# ETH10M100M_RMII_DP83825.net
KiCad netlist of a schematic drawn in Altium Designer
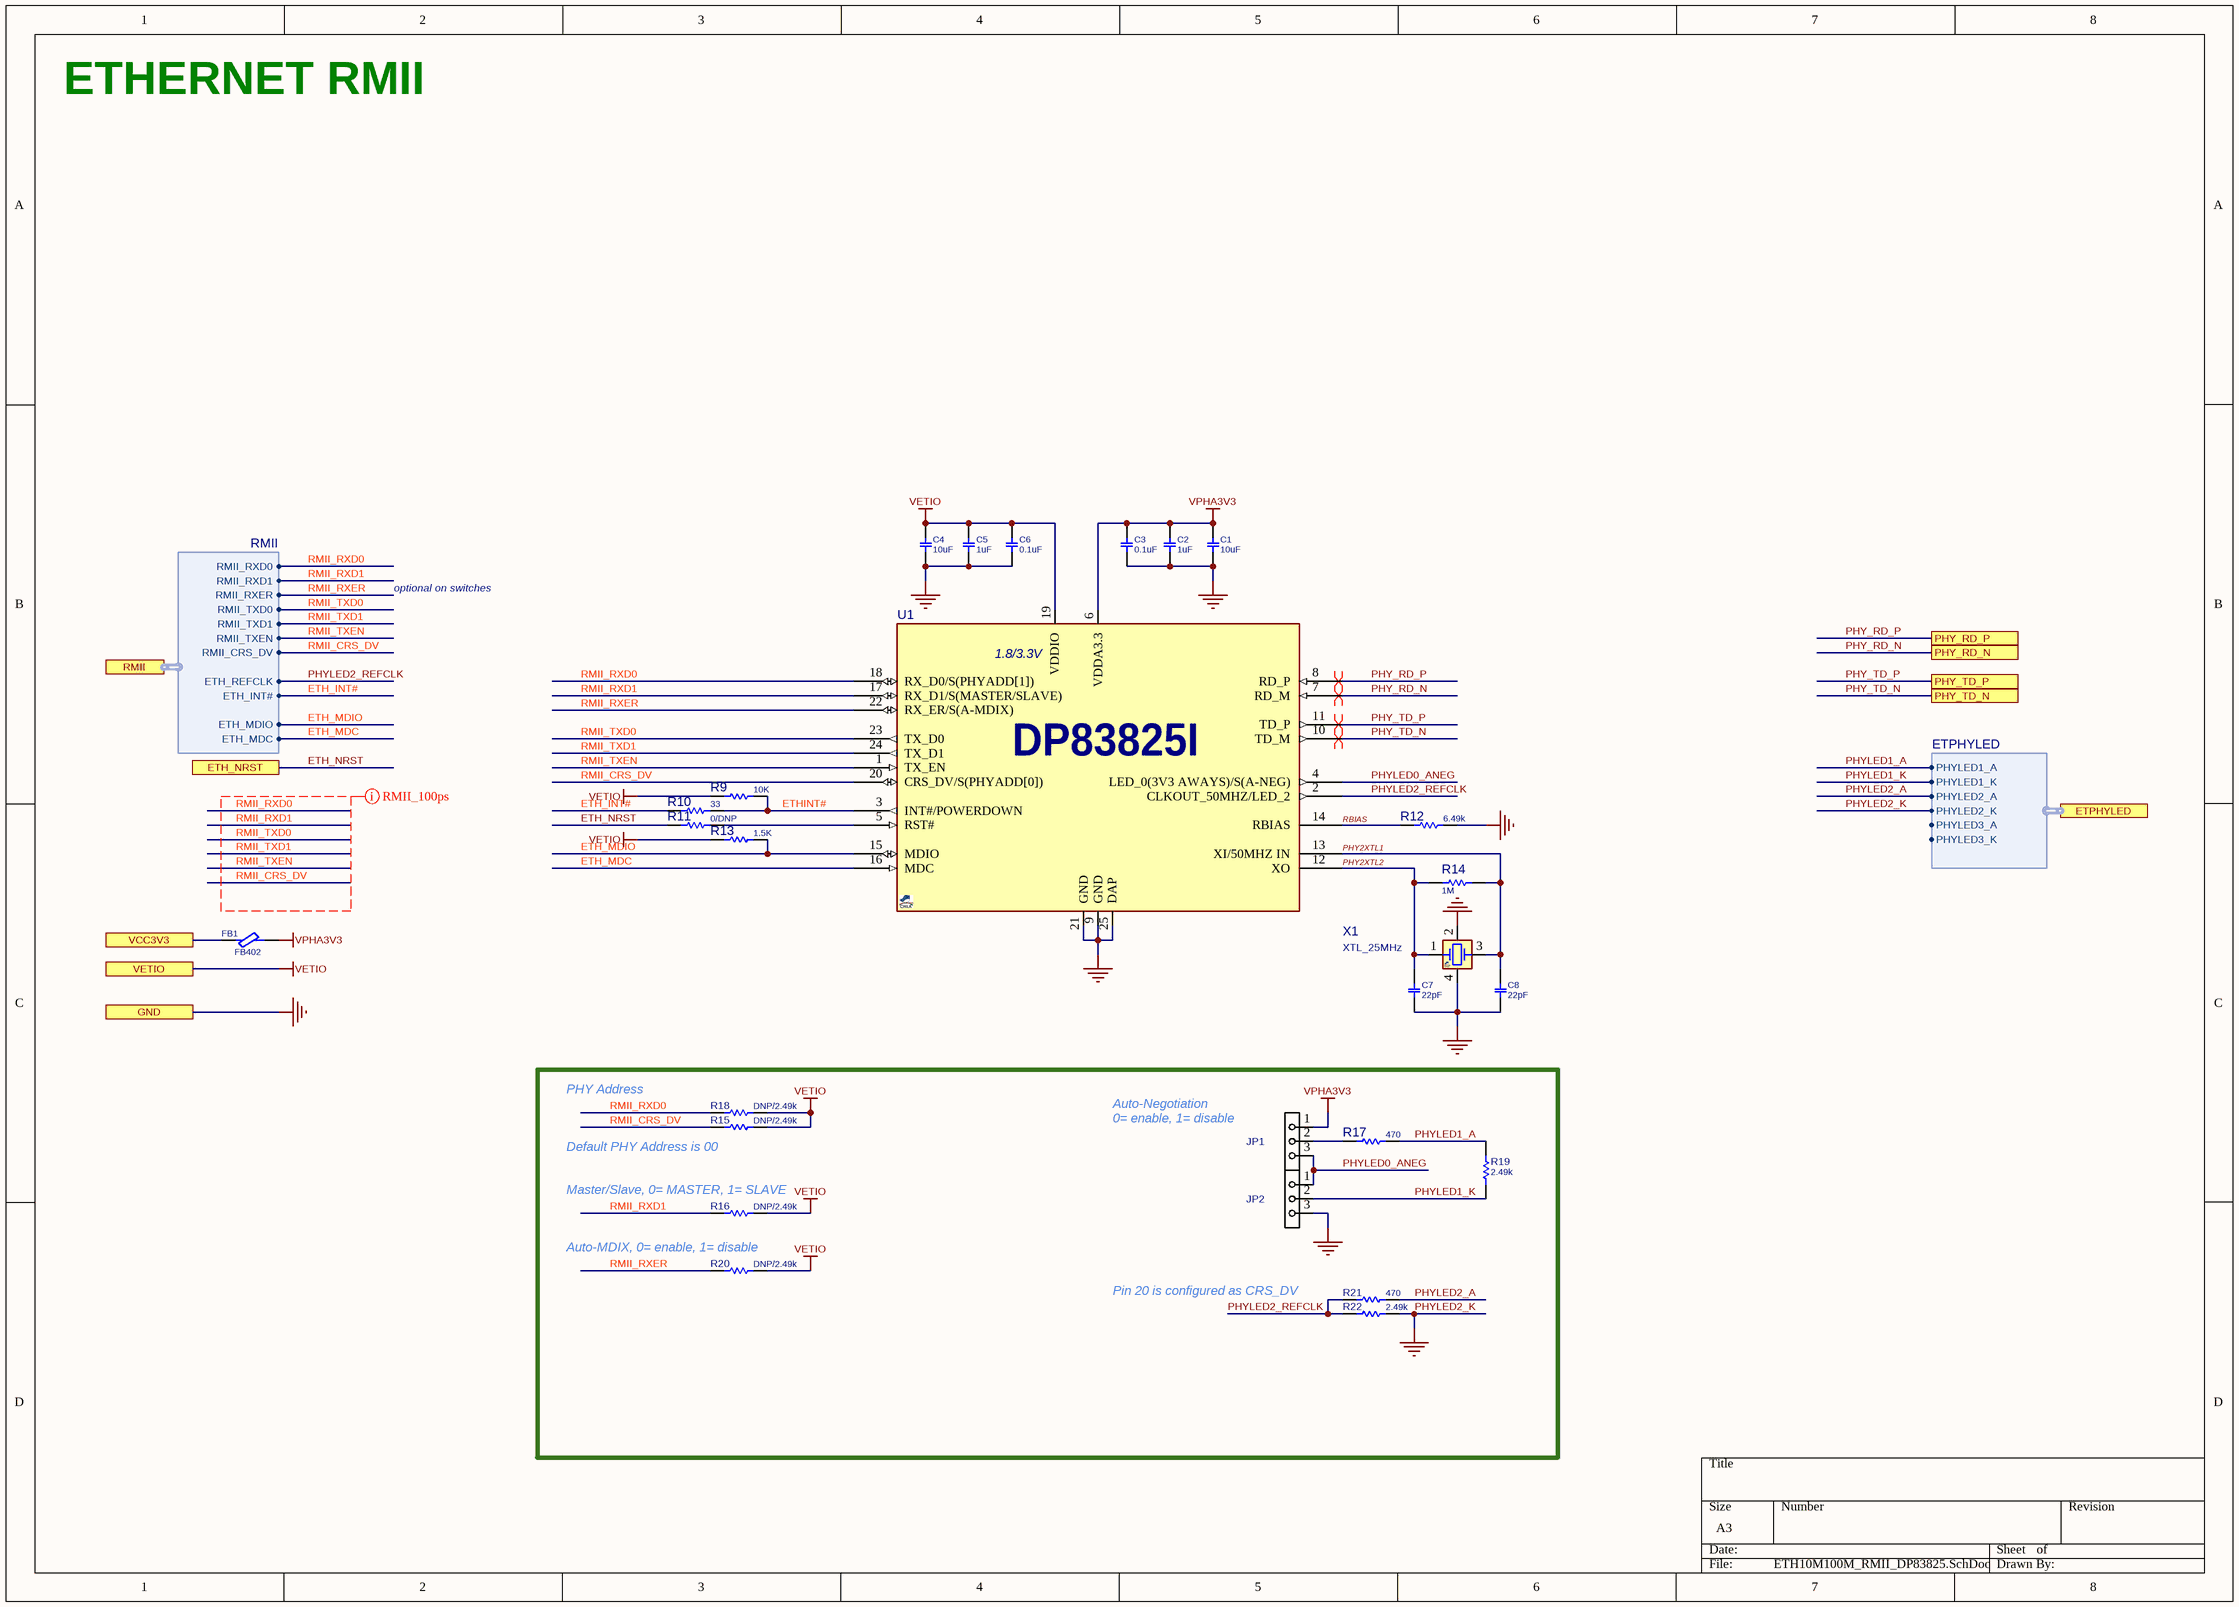
[diagram p0: ETH10M100M_RMII_DP83825.SchDoc]

(export (version "E")
  (design (tool "Eeschema 10.0.6"))
  (components
    (comp (ref "C1")
      (value "10uF")
      (footprint "C0402")
      (description "CAP, MLCC")
      (libsource (lib "mlcc_smd_passive") (part "CAP_SMD_MLCC_100n50TDK"))
    )
    (comp (ref "C2")
      (value "1uF")
      (footprint "C0402")
      (description "CAP, MLCC")
      (libsource (lib "mlcc_smd_passive") (part "CAP_SMD_MLCC_100n50TDK"))
    )
    (comp (ref "C3")
      (value "0.1uF")
      (footprint "C0402")
      (description "CAP, MLCC")
      (libsource (lib "mlcc_smd_passive") (part "CAP_SMD_MLCC_100n50TDK"))
    )
    (comp (ref "C4")
      (value "10uF")
      (footprint "C0402")
      (description "CAP, MLCC")
      (libsource (lib "mlcc_smd_passive") (part "CAP_SMD_MLCC_100n50TDK"))
    )
    (comp (ref "C5")
      (value "1uF")
      (footprint "C0402")
      (description "CAP, MLCC")
      (libsource (lib "mlcc_smd_passive") (part "CAP_SMD_MLCC_100n50TDK"))
    )
    (comp (ref "C6")
      (value "0.1uF")
      (footprint "C0402")
      (description "CAP, MLCC")
      (libsource (lib "mlcc_smd_passive") (part "CAP_SMD_MLCC_100n50TDK"))
    )
    (comp (ref "C7")
      (value "22pF")
      (footprint "C0402")
      (description "CAP, MLCC")
      (libsource (lib "mlcc_smd_passive") (part "CAP_SMD_MLCC_100n50TDK"))
    )
    (comp (ref "C8")
      (value "22pF")
      (footprint "C0402")
      (description "CAP, MLCC")
      (libsource (lib "mlcc_smd_passive") (part "CAP_SMD_MLCC_100n50TDK"))
    )
    (comp (ref "FB1")
      (value "FB402")
      (footprint "L0402")
      (description "FERRITE_Bead")
      (libsource (lib "emi_filter") (part "FBEAD_SMD_BLM18KG601"))
    )
    (comp (ref "JP1")
      (value "JMPHDR3PIN")
      (footprint "JP_3_60W")
      (description "JUMPER, HEADER 3PIN")
      (fields (field (name "MANF") "MANF") (field (name "MANF_P#") "MANF_P#"))
      (libsource (lib "test-tp_jumper") (part "JUMPER_SOLDER_3P"))
    )
    (comp (ref "JP2")
      (value "JMPHDR3PIN")
      (footprint "JP_3_60W")
      (description "JUMPER, HEADER 3PIN")
      (fields (field (name "MANF") "MANF") (field (name "MANF_P#") "MANF_P#"))
      (libsource (lib "test-tp_jumper") (part "JUMPER_SOLDER_3P"))
    )
    (comp (ref "R9")
      (value "10K")
      (footprint "R0402")
      (description "RESISTOR, SMD, THICK FILM, YAGEO")
      (fields (field (name "MANF_P#") "RC0402FR-071KL") (field (name "MANF") "Yageo"))
      (libsource (lib "res_smd_Yageo0402_thickfilm") (part "RES_SMD_1K_0402YK"))
    )
    (comp (ref "R10")
      (value "33")
      (footprint "R0402")
      (description "RESISTOR, SMD, THICK FILM, YAGEO")
      (fields (field (name "MANF_P#") "RC0402FR-071KL") (field (name "MANF") "Yageo"))
      (libsource (lib "res_smd_Yageo0402_thickfilm") (part "RES_SMD_1K_0402YK"))
    )
    (comp (ref "R11")
      (value "0/DNP")
      (footprint "R0402")
      (description "RESISTOR, SMD, THICK FILM, YAGEO")
      (fields (field (name "MANF_P#") "RC0402FR-071KL") (field (name "MANF") "Yageo"))
      (libsource (lib "res_smd_Yageo0402_thickfilm") (part "RES_SMD_1K_0402YK"))
    )
    (comp (ref "R12")
      (value "6.49k")
      (footprint "R0402")
      (description "RESISTOR, SMD, THICK FILM, YAGEO")
      (fields (field (name "MANF_P#") "RC0402FR-071KL") (field (name "MANF") "Yageo"))
      (libsource (lib "res_smd_Yageo0402_thickfilm") (part "RES_SMD_1K_0402YK"))
    )
    (comp (ref "R13")
      (value "1.5K")
      (footprint "R0402")
      (description "RESISTOR, SMD, THICK FILM, YAGEO")
      (fields (field (name "MANF_P#") "RC0402FR-071KL") (field (name "MANF") "Yageo"))
      (libsource (lib "res_smd_Yageo0402_thickfilm") (part "RES_SMD_1K_0402YK"))
    )
    (comp (ref "R14")
      (value "1M")
      (footprint "R0402")
      (description "RESISTOR, SMD")
      (fields (field (name "MANF") "Yageo") (field (name "MANF_P#") "RC0402FR-071ML"))
      (libsource (lib "res_smd_KoaSpeer0402") (part "RES_SMD_10K_0402"))
    )
    (comp (ref "R15")
      (value "DNP/2.49k")
      (footprint "R0402")
      (description "RESISTOR, SMD, THICK FILM, YAGEO")
      (fields (field (name "MANF_P#") "RC0402FR-071KL") (field (name "MANF") "Yageo"))
      (libsource (lib "res_smd_Yageo0402_thickfilm") (part "RES_SMD_1K_0402YK"))
    )
    (comp (ref "R16")
      (value "DNP/2.49k")
      (footprint "R0402")
      (description "RESISTOR, SMD, THICK FILM, YAGEO")
      (fields (field (name "MANF_P#") "RC0402FR-071KL") (field (name "MANF") "Yageo"))
      (libsource (lib "res_smd_Yageo0402_thickfilm") (part "RES_SMD_1K_0402YK"))
    )
    (comp (ref "R17")
      (value "470")
      (footprint "R0402")
      (description "RESISTOR, SMD, THICK FILM, YAGEO")
      (fields (field (name "MANF_P#") "RC0402FR-071KL") (field (name "MANF") "Yageo"))
      (libsource (lib "res_smd_Yageo0402_thickfilm") (part "RES_SMD_1K_0402YK"))
    )
    (comp (ref "R18")
      (value "DNP/2.49k")
      (footprint "R0402")
      (description "RESISTOR, SMD, THICK FILM, YAGEO")
      (fields (field (name "MANF_P#") "RC0402FR-071KL") (field (name "MANF") "Yageo"))
      (libsource (lib "res_smd_Yageo0402_thickfilm") (part "RES_SMD_1K_0402YK"))
    )
    (comp (ref "R19")
      (value "2.49k")
      (footprint "R0402")
      (description "RESISTOR, SMD, THICK FILM, YAGEO")
      (fields (field (name "MANF_P#") "RC0402FR-071KL") (field (name "MANF") "Yageo"))
      (libsource (lib "res_smd_Yageo0402_thickfilm") (part "RES_SMD_1K_0402YK"))
    )
    (comp (ref "R20")
      (value "DNP/2.49k")
      (footprint "R0402")
      (description "RESISTOR, SMD, THICK FILM, YAGEO")
      (fields (field (name "MANF_P#") "RC0402FR-071KL") (field (name "MANF") "Yageo"))
      (libsource (lib "res_smd_Yageo0402_thickfilm") (part "RES_SMD_1K_0402YK"))
    )
    (comp (ref "R21")
      (value "470")
      (footprint "R0402")
      (description "RESISTOR, SMD, THICK FILM, YAGEO")
      (fields (field (name "MANF_P#") "RC0402FR-071KL") (field (name "MANF") "Yageo"))
      (libsource (lib "res_smd_Yageo0402_thickfilm") (part "RES_SMD_1K_0402YK"))
    )
    (comp (ref "R22")
      (value "2.49k")
      (footprint "R0402")
      (description "RESISTOR, SMD, THICK FILM, YAGEO")
      (fields (field (name "MANF_P#") "RC0402FR-071KL") (field (name "MANF") "Yageo"))
      (libsource (lib "res_smd_Yageo0402_thickfilm") (part "RES_SMD_1K_0402YK"))
    )
    (comp (ref "U1")
      (value "DP83825I")
      (footprint "QFN40_24T_3X3_RMQ")
      (description "Ethernet Transceiver, 10/100, RMII")
      (fields (field (name "MANF") "Texas Instruments") (field (name "MANF_P#") "DP83825IRMQ"))
      (libsource (lib "ethernet") (part "DP83825I_QFN24"))
    )
    (comp (ref "X1")
      (value "XTL_25MHz")
      (footprint "XTL_4_2016")
      (description "CRYSTAL 25.00 MHZ")
      (fields (field (name "MANF_P#") "china"))
      (libsource (lib "crystal_osc") (part "XTL_4_25MHz_3225"))
    )
  )
  (nets
    (net (code "3") (name "/ETHINT#") (class "Default")
      (node (ref "R10") (pin "1") (pinfunction "1_1") (pintype "passive"))
      (node (ref "R9") (pin "1") (pinfunction "1_1") (pintype "passive"))
      (node (ref "U1") (pin "3") (pinfunction "INT#/POWERDOWN_3") (pintype "output"))
    )
    (net (code "4") (name "/ETH_INT#") (class "Default")
      (node (ref "R10") (pin "2") (pinfunction "2_2") (pintype "passive"))
    )
    (net (code "5") (name "/ETH_MDC") (class "Default")
      (node (ref "U1") (pin "16") (pinfunction "MDC_16") (pintype "input"))
    )
    (net (code "6") (name "/ETH_MDIO") (class "Default")
      (node (ref "R13") (pin "1") (pinfunction "1_1") (pintype "passive"))
      (node (ref "U1") (pin "15") (pinfunction "MDIO_15") (pintype "bidirectional"))
    )
    (net (code "7") (name "/ETH_NRST") (class "Default")
      (node (ref "R11") (pin "2") (pinfunction "2_2") (pintype "passive"))
    )
    (net (code "8") (name "/PHY2XTL1") (class "Default")
      (node (ref "C8") (pin "1") (pinfunction "1_1") (pintype "passive"))
      (node (ref "R14") (pin "2") (pinfunction "2_2") (pintype "passive"))
      (node (ref "U1") (pin "13") (pinfunction "XI/50MHZ_IN_13") (pintype "passive"))
      (node (ref "X1") (pin "3") (pinfunction "XB_3") (pintype "passive"))
    )
    (net (code "9") (name "/PHY2XTL2") (class "Default")
      (node (ref "C7") (pin "1") (pinfunction "1_1") (pintype "passive"))
      (node (ref "R14") (pin "1") (pinfunction "1_1") (pintype "passive"))
      (node (ref "U1") (pin "12") (pinfunction "XO_12") (pintype "passive"))
      (node (ref "X1") (pin "1") (pinfunction "XA_1") (pintype "passive"))
    )
    (net (code "10") (name "/PHYLED0_ANEG") (class "Default")
      (node (ref "JP1") (pin "3") (pinfunction "3_3") (pintype "passive"))
      (node (ref "JP2") (pin "1") (pinfunction "1_1") (pintype "passive"))
      (node (ref "U1") (pin "4") (pinfunction "LED_0(3V3_AWAYS)/S(A-NEG)_4") (pintype "output"))
    )
    (net (code "11") (name "/PHYLED1_A") (class "Default")
      (node (ref "R17") (pin "2") (pinfunction "2_2") (pintype "passive"))
      (node (ref "R19") (pin "2") (pinfunction "2_2") (pintype "passive"))
    )
    (net (code "12") (name "/PHYLED1_K") (class "Default")
      (node (ref "JP2") (pin "2") (pinfunction "2_2") (pintype "passive"))
      (node (ref "R19") (pin "1") (pinfunction "1_1") (pintype "passive"))
    )
    (net (code "13") (name "/PHYLED2_A") (class "Default")
      (node (ref "R21") (pin "2") (pinfunction "2_2") (pintype "passive"))
    )
    (net (code "14") (name "/PHYLED2_REFCLK") (class "Default")
      (node (ref "R21") (pin "1") (pinfunction "1_1") (pintype "passive"))
      (node (ref "R22") (pin "2") (pinfunction "2_2") (pintype "passive"))
      (node (ref "U1") (pin "2") (pinfunction "CLKOUT_50MHZ/LED_2_2") (pintype "output"))
    )
    (net (code "15") (name "/PHY_RD_N") (class "Default")
      (node (ref "U1") (pin "7") (pinfunction "RD_M_7") (pintype "input"))
    )
    (net (code "16") (name "/PHY_RD_P") (class "Default")
      (node (ref "U1") (pin "8") (pinfunction "RD_P_8") (pintype "input"))
    )
    (net (code "17") (name "/PHY_TD_N") (class "Default")
      (node (ref "U1") (pin "10") (pinfunction "TD_M_10") (pintype "output"))
    )
    (net (code "18") (name "/PHY_TD_P") (class "Default")
      (node (ref "U1") (pin "11") (pinfunction "TD_P_11") (pintype "output"))
    )
    (net (code "19") (name "/RBIAS") (class "Default")
      (node (ref "R12") (pin "2") (pinfunction "2_2") (pintype "passive"))
      (node (ref "U1") (pin "14") (pinfunction "RBIAS_14") (pintype "passive"))
    )
    (net (code "20") (name "/RMII_CRS_DV") (class "Default")
      (node (ref "R15") (pin "1") (pinfunction "1_1") (pintype "passive"))
      (node (ref "U1") (pin "20") (pinfunction "CRS_DV/S(PHYADD[0])_20") (pintype "bidirectional"))
    )
    (net (code "21") (name "/RMII_RXD0") (class "Default")
      (node (ref "R18") (pin "1") (pinfunction "1_1") (pintype "passive"))
      (node (ref "U1") (pin "18") (pinfunction "RX_D0/S(PHYADD[1])_18") (pintype "bidirectional"))
    )
    (net (code "22") (name "/RMII_RXD1") (class "Default")
      (node (ref "R16") (pin "1") (pinfunction "1_1") (pintype "passive"))
      (node (ref "U1") (pin "17") (pinfunction "RX_D1/S(MASTER/SLAVE)_17") (pintype "bidirectional"))
    )
    (net (code "23") (name "/RMII_RXER") (class "Default")
      (node (ref "R20") (pin "2") (pinfunction "2_2") (pintype "passive"))
      (node (ref "U1") (pin "22") (pinfunction "RX_ER/S(A-MDIX)_22") (pintype "bidirectional"))
    )
    (net (code "24") (name "/RMII_TXD0") (class "Default")
      (node (ref "U1") (pin "23") (pinfunction "TX_D0_23") (pintype "output"))
    )
    (net (code "25") (name "/RMII_TXD1") (class "Default")
      (node (ref "U1") (pin "24") (pinfunction "TX_D1_24") (pintype "output"))
    )
    (net (code "26") (name "/RMII_TXEN") (class "Default")
      (node (ref "U1") (pin "1") (pinfunction "TX_EN_1") (pintype "input"))
    )
    (net (code "27") (name "/VCC3V3") (class "Default")
      (node (ref "FB1") (pin "1") (pinfunction "1_1") (pintype "passive"))
    )
    (net (code "30") (name "GND") (class "Default")
      (node (ref "C1") (pin "2") (pinfunction "2_2") (pintype "passive"))
      (node (ref "C2") (pin "2") (pinfunction "2_2") (pintype "passive"))
      (node (ref "C3") (pin "2") (pinfunction "2_2") (pintype "passive"))
      (node (ref "C4") (pin "2") (pinfunction "2_2") (pintype "passive"))
      (node (ref "C5") (pin "2") (pinfunction "2_2") (pintype "passive"))
      (node (ref "C6") (pin "2") (pinfunction "2_2") (pintype "passive"))
      (node (ref "C7") (pin "2") (pinfunction "2_2") (pintype "passive"))
      (node (ref "C8") (pin "2") (pinfunction "2_2") (pintype "passive"))
      (node (ref "JP2") (pin "3") (pinfunction "3_3") (pintype "passive"))
      (node (ref "R12") (pin "1") (pinfunction "1_1") (pintype "passive"))
      (node (ref "R22") (pin "1") (pinfunction "1_1") (pintype "passive"))
      (node (ref "U1") (pin "21") (pinfunction "GND_21") (pintype "power_in"))
      (node (ref "U1") (pin "25") (pinfunction "DAP_25") (pintype "power_in"))
      (node (ref "U1") (pin "9") (pinfunction "GND_9") (pintype "power_in"))
      (node (ref "X1") (pin "2") (pinfunction "GND1_2") (pintype "passive"))
      (node (ref "X1") (pin "4") (pinfunction "GND2_4") (pintype "passive"))
    )
    (net (code "31") (name "Net-(JP1-Pad2)") (class "Default")
      (node (ref "JP1") (pin "2") (pinfunction "2_2") (pintype "passive"))
      (node (ref "R17") (pin "1") (pinfunction "1_1") (pintype "passive"))
    )
    (net (code "32") (name "Net-(U1-RST#)") (class "Default")
      (node (ref "R11") (pin "1") (pinfunction "1_1") (pintype "passive"))
      (node (ref "U1") (pin "5") (pinfunction "RST#_5") (pintype "input"))
    )
    (net (code "33") (name "VETIO") (class "Default")
      (node (ref "C4") (pin "1") (pinfunction "1_1") (pintype "passive"))
      (node (ref "C5") (pin "1") (pinfunction "1_1") (pintype "passive"))
      (node (ref "C6") (pin "1") (pinfunction "1_1") (pintype "passive"))
      (node (ref "R13") (pin "2") (pinfunction "2_2") (pintype "passive"))
      (node (ref "R15") (pin "2") (pinfunction "2_2") (pintype "passive"))
      (node (ref "R16") (pin "2") (pinfunction "2_2") (pintype "passive"))
      (node (ref "R18") (pin "2") (pinfunction "2_2") (pintype "passive"))
      (node (ref "R20") (pin "1") (pinfunction "1_1") (pintype "passive"))
      (node (ref "R9") (pin "2") (pinfunction "2_2") (pintype "passive"))
      (node (ref "U1") (pin "19") (pinfunction "VDDIO_19") (pintype "power_in"))
    )
    (net (code "34") (name "VPHA3V3") (class "Default")
      (node (ref "C1") (pin "1") (pinfunction "1_1") (pintype "passive"))
      (node (ref "C2") (pin "1") (pinfunction "1_1") (pintype "passive"))
      (node (ref "C3") (pin "1") (pinfunction "1_1") (pintype "passive"))
      (node (ref "FB1") (pin "2") (pinfunction "2_2") (pintype "passive"))
      (node (ref "JP1") (pin "1") (pinfunction "1_1") (pintype "passive"))
      (node (ref "U1") (pin "6") (pinfunction "VDDA3.3_6") (pintype "power_in"))
    )
  )
)
